# G2-PMS.net
KiCad netlist of a schematic drawn in Altium Designer
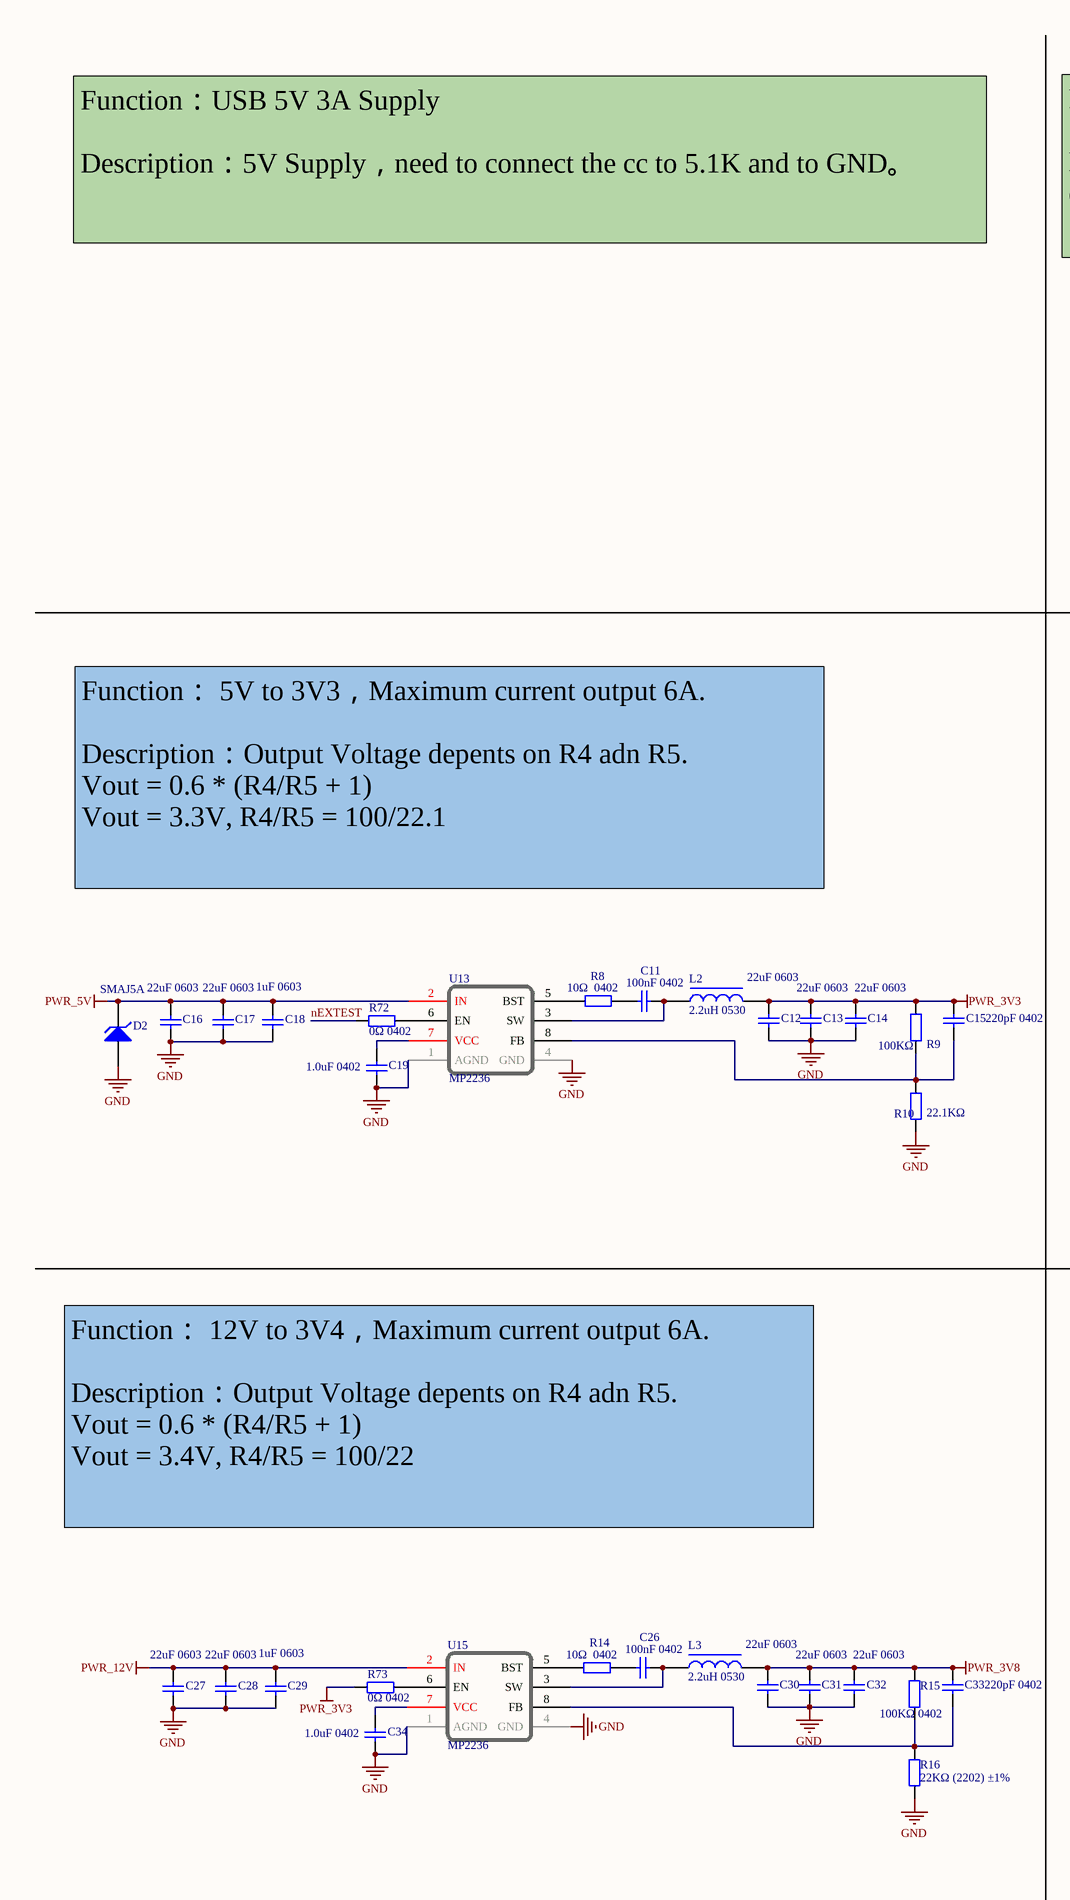
[diagram p0: G2-PMS.SchDoc, left]
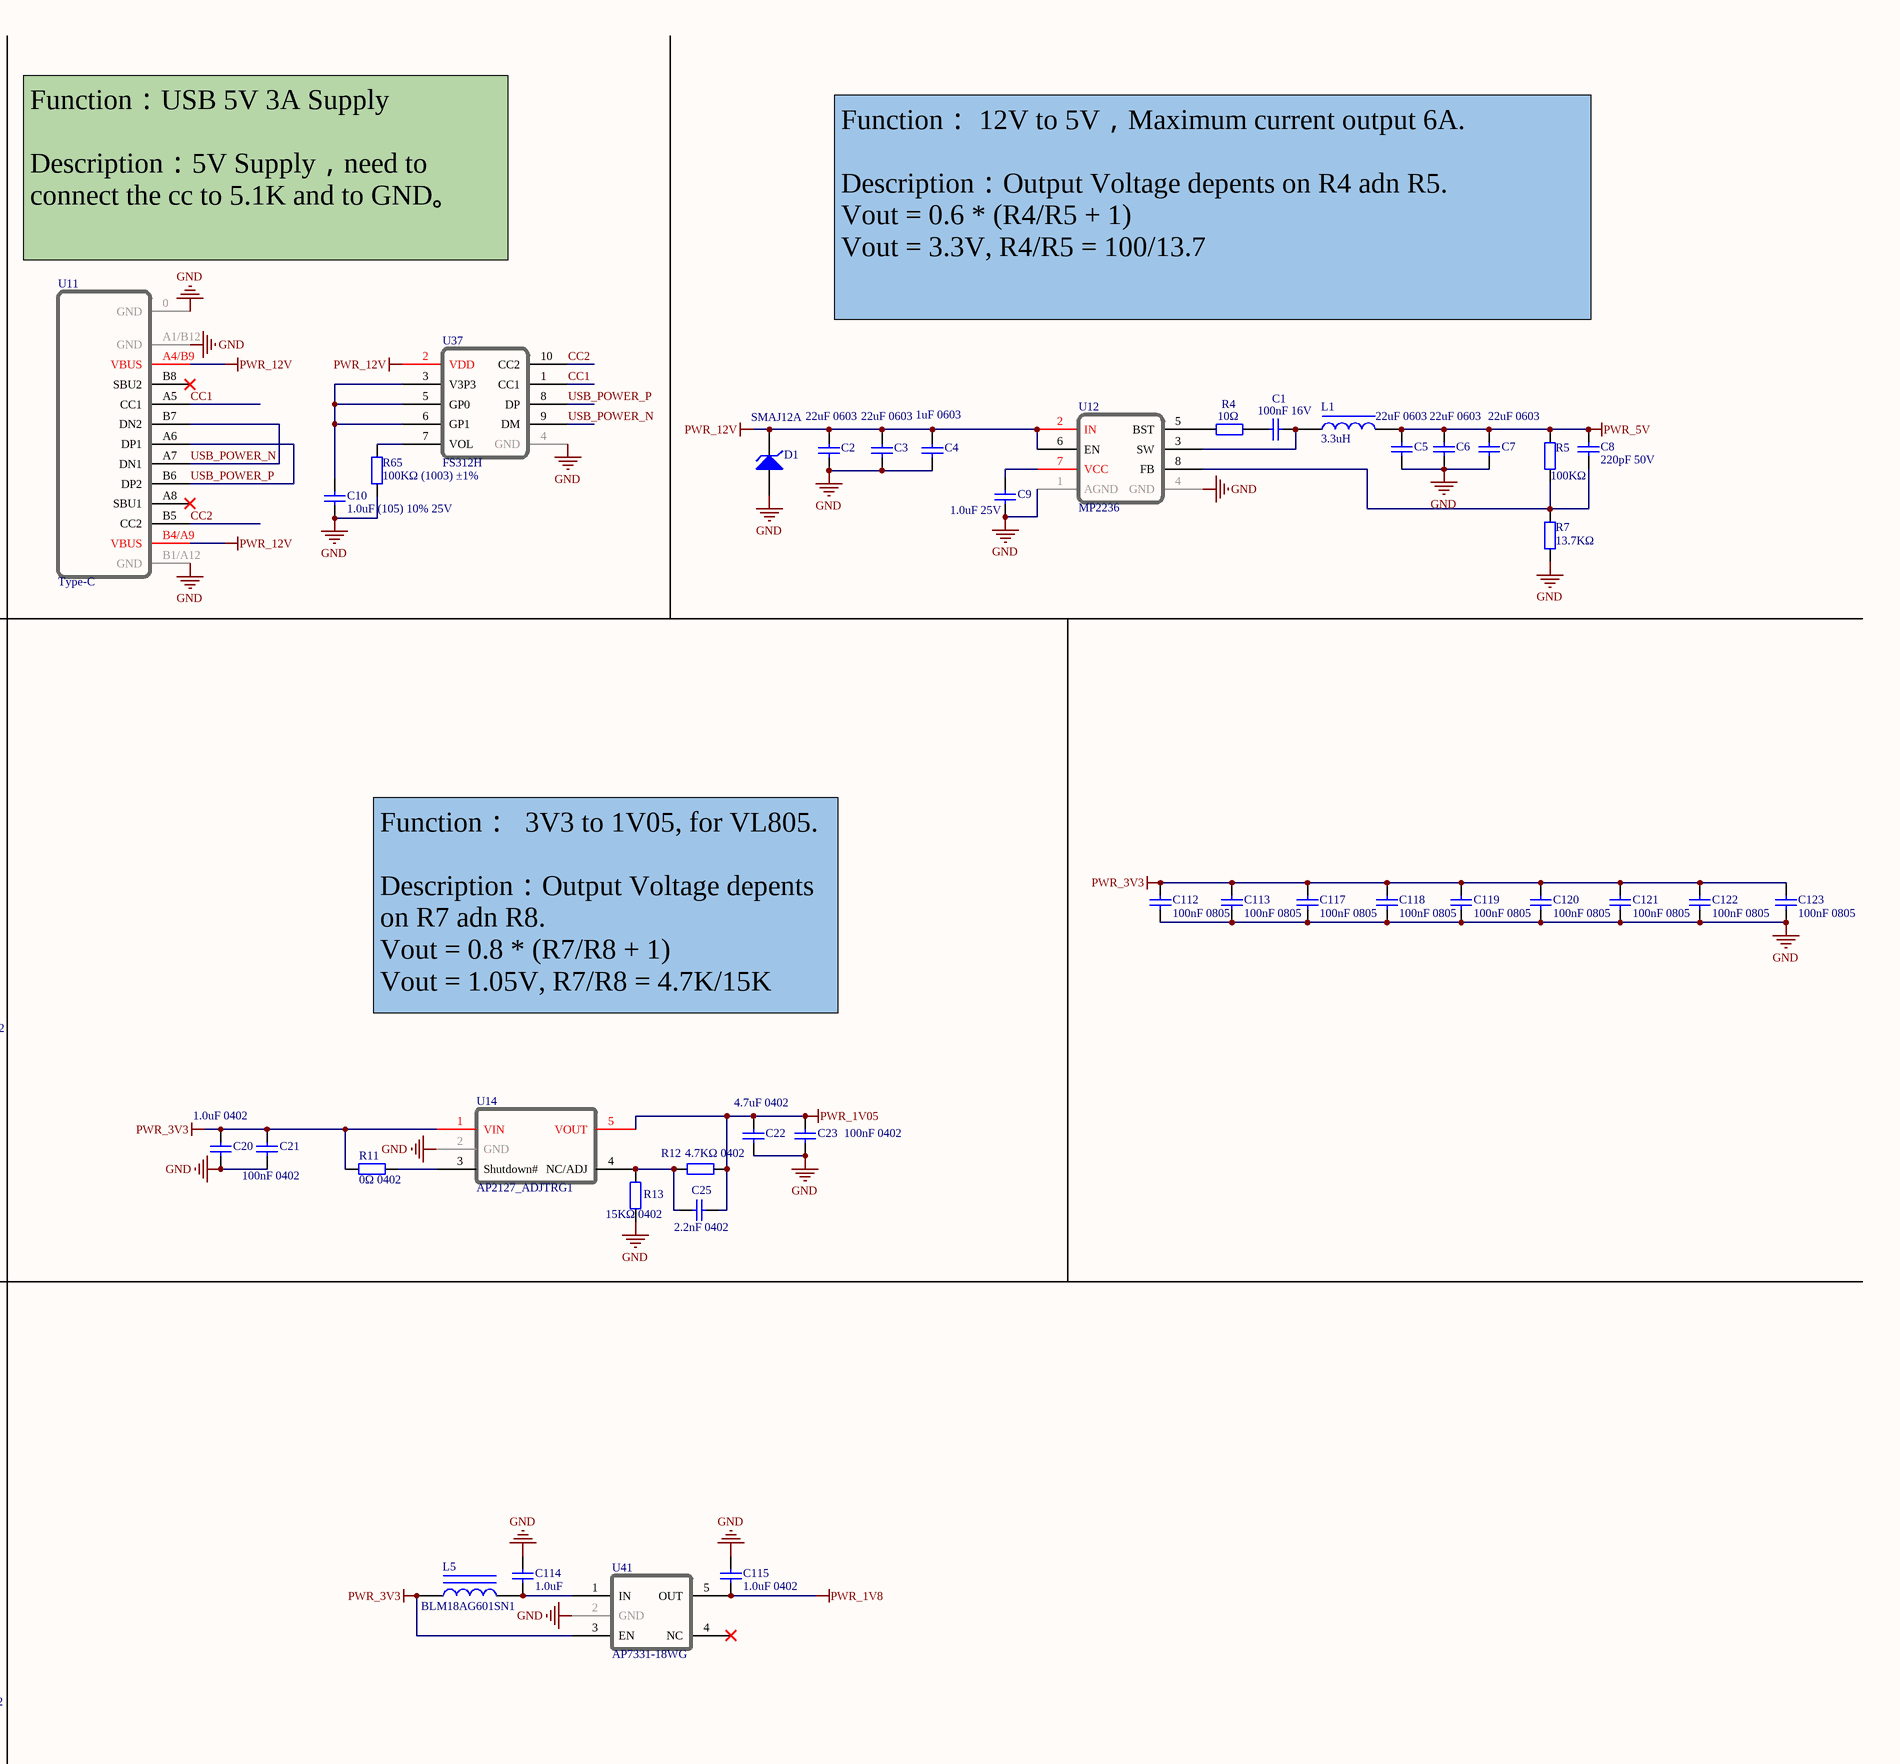
[diagram p1: G2-PMS.SchDoc, right]

(export (version "E")
  (design (tool "Eeschema 10.0.6"))
  (components
    (comp (ref "C1")
      (value "100nF 16V")
      (footprint "0402_C")
      (description "贴片电容")
      (libsource (lib "Miscellaneous Devices LC") (part "0402 100nF (104) 10% 16V"))
    )
    (comp (ref "C2")
      (value "22uF 0603")
      (footprint "0603_C")
      (description "贴片电容")
      (libsource (lib "Miscellaneous Devices LC") (part "0603 22uF (226) 20% 6.3V"))
    )
    (comp (ref "C3")
      (value "22uF 0603")
      (footprint "0603_C")
      (description "贴片电容")
      (libsource (lib "Miscellaneous Devices LC") (part "0603 22uF (226) 20% 6.3V"))
    )
    (comp (ref "C4")
      (value "1uF 0603")
      (footprint "0603_C")
      (description "贴片电容")
      (libsource (lib "Miscellaneous Devices LC") (part "0603 1uF (105) 10% 50V"))
    )
    (comp (ref "C5")
      (value "22uF 0603")
      (footprint "0603_C")
      (description "贴片电容")
      (libsource (lib "Miscellaneous Devices LC") (part "0603 22uF (226) 20% 6.3V"))
    )
    (comp (ref "C6")
      (value "22uF 0603")
      (footprint "0603_C")
      (description "贴片电容")
      (libsource (lib "Miscellaneous Devices LC") (part "0603 22uF (226) 20% 6.3V"))
    )
    (comp (ref "C7")
      (value "22uF 0603")
      (footprint "0603_C")
      (description "贴片电容")
      (libsource (lib "Miscellaneous Devices LC") (part "0603 22uF (226) 20% 6.3V"))
    )
    (comp (ref "C8")
      (value "220pF 50V")
      (footprint "0402_C")
      (description "贴片电容")
      (libsource (lib "Miscellaneous Devices LC") (part "0402 220pF (221) 10% 50V"))
    )
    (comp (ref "C9")
      (value "1.0uF 25V")
      (footprint "0402_C")
      (description "贴片电容")
      (libsource (lib "Miscellaneous Devices LC") (part "0402 1.0uF (105) 10% 25V"))
    )
    (comp (ref "C10")
      (value "1.0uF (105) 10% 25V")
      (footprint "0402_C")
      (description "贴片电容")
      (libsource (lib "Miscellaneous Devices LC") (part "0402 1.0uF (105) 10% 25V"))
    )
    (comp (ref "C11")
      (value "100nF 0402")
      (footprint "0402_C")
      (description "贴片电容")
      (libsource (lib "Miscellaneous Devices LC") (part "0402 100nF (104) 10% 16V"))
    )
    (comp (ref "C12")
      (value "22uF 0603")
      (footprint "0603_C")
      (description "贴片电容")
      (libsource (lib "Miscellaneous Devices LC") (part "0603 22uF (226) 20% 6.3V"))
    )
    (comp (ref "C13")
      (value "22uF 0603")
      (footprint "0603_C")
      (description "贴片电容")
      (libsource (lib "Miscellaneous Devices LC") (part "0603 22uF (226) 20% 6.3V"))
    )
    (comp (ref "C14")
      (value "22uF 0603")
      (footprint "0603_C")
      (description "贴片电容")
      (libsource (lib "Miscellaneous Devices LC") (part "0603 22uF (226) 20% 6.3V"))
    )
    (comp (ref "C15")
      (value "220pF 0402")
      (footprint "0402_C")
      (description "贴片电容")
      (libsource (lib "Miscellaneous Devices LC") (part "0402 220pF (221) 10% 50V"))
    )
    (comp (ref "C16")
      (value "22uF 0603")
      (footprint "0603_C")
      (description "贴片电容")
      (libsource (lib "Miscellaneous Devices LC") (part "0603 22uF (226) 20% 6.3V"))
    )
    (comp (ref "C17")
      (value "22uF 0603")
      (footprint "0603_C")
      (description "贴片电容")
      (libsource (lib "Miscellaneous Devices LC") (part "0603 22uF (226) 20% 6.3V"))
    )
    (comp (ref "C18")
      (value "1uF 0603")
      (footprint "0603_C")
      (description "贴片电容")
      (libsource (lib "Miscellaneous Devices LC") (part "0603 1uF (105) 10% 50V"))
    )
    (comp (ref "C19")
      (value "1.0uF 0402")
      (footprint "0402_C")
      (description "贴片电容")
      (libsource (lib "Miscellaneous Devices LC") (part "0402 1.0uF (105) 10% 25V"))
    )
    (comp (ref "C20")
      (value "1.0uF 0402")
      (footprint "0402_C")
      (description "贴片电容")
      (libsource (lib "Miscellaneous Devices LC") (part "0402 1.0uF (105) 10% 25V"))
    )
    (comp (ref "C21")
      (value "100nF 0402")
      (footprint "0402_C")
      (description "贴片电容")
      (libsource (lib "Miscellaneous Devices LC") (part "0402 100nF (104) 10% 16V"))
    )
    (comp (ref "C22")
      (value "4.7uF 0402")
      (footprint "0402_C")
      (description "贴片电容")
      (libsource (lib "Miscellaneous Devices LC") (part "0402 4.7uF (475) 20% 10V"))
    )
    (comp (ref "C23")
      (value "100nF 0402")
      (footprint "0402_C")
      (description "贴片电容")
      (libsource (lib "Miscellaneous Devices LC") (part "0402 100nF (104) 10% 16V"))
    )
    (comp (ref "C25")
      (value "2.2nF 0402")
      (footprint "0402_C")
      (description "贴片电容")
      (libsource (lib "Miscellaneous Devices LC") (part "0402 2.2nF (222) 10% 50V"))
    )
    (comp (ref "C26")
      (value "100nF 0402")
      (footprint "0402_C")
      (description "贴片电容")
      (libsource (lib "Miscellaneous Devices LC") (part "0402 100nF (104) 10% 16V"))
    )
    (comp (ref "C27")
      (value "22uF 0603")
      (footprint "0603_C")
      (description "贴片电容")
      (libsource (lib "Miscellaneous Devices LC") (part "0603 22uF (226) 20% 6.3V"))
    )
    (comp (ref "C28")
      (value "22uF 0603")
      (footprint "0603_C")
      (description "贴片电容")
      (libsource (lib "Miscellaneous Devices LC") (part "0603 22uF (226) 20% 6.3V"))
    )
    (comp (ref "C29")
      (value "1uF 0603")
      (footprint "0603_C")
      (description "贴片电容")
      (libsource (lib "Miscellaneous Devices LC") (part "0603 1uF (105) 10% 50V"))
    )
    (comp (ref "C30")
      (value "22uF 0603")
      (footprint "0603_C")
      (description "贴片电容")
      (libsource (lib "Miscellaneous Devices LC") (part "0603 22uF (226) 20% 6.3V"))
    )
    (comp (ref "C31")
      (value "22uF 0603")
      (footprint "0603_C")
      (description "贴片电容")
      (libsource (lib "Miscellaneous Devices LC") (part "0603 22uF (226) 20% 6.3V"))
    )
    (comp (ref "C32")
      (value "22uF 0603")
      (footprint "0603_C")
      (description "贴片电容")
      (libsource (lib "Miscellaneous Devices LC") (part "0603 22uF (226) 20% 6.3V"))
    )
    (comp (ref "C33")
      (value "220pF 0402")
      (footprint "0402_C")
      (description "贴片电容")
      (libsource (lib "Miscellaneous Devices LC") (part "0402 220pF (221) 10% 50V"))
    )
    (comp (ref "C34")
      (value "1.0uF 0402")
      (footprint "0402_C")
      (description "贴片电容")
      (libsource (lib "Miscellaneous Devices LC") (part "0402 1.0uF (105) 10% 25V"))
    )
    (comp (ref "C112")
      (value "100nF 0805")
      (footprint "0805_C")
      (description "贴片电容")
      (libsource (lib "Miscellaneous Devices LC") (part "0805 100nF(104) 10% 50V"))
    )
    (comp (ref "C113")
      (value "100nF 0805")
      (footprint "0805_C")
      (description "贴片电容")
      (libsource (lib "Miscellaneous Devices LC") (part "0805 100nF(104) 10% 50V"))
    )
    (comp (ref "C114")
      (value "1.0uF")
      (footprint "0402_C")
      (description "贴片电容")
      (libsource (lib "Miscellaneous Devices LC") (part "0402 1.0uF (105) 10% 25V"))
    )
    (comp (ref "C115")
      (value "1.0uF 0402")
      (footprint "0402_C")
      (description "贴片电容")
      (libsource (lib "Miscellaneous Devices LC") (part "0402 1.0uF (105) 10% 25V"))
    )
    (comp (ref "C117")
      (value "100nF 0805")
      (footprint "0805_C")
      (description "贴片电容")
      (libsource (lib "Miscellaneous Devices LC") (part "0805 100nF(104) 10% 50V"))
    )
    (comp (ref "C118")
      (value "100nF 0805")
      (footprint "0805_C")
      (description "贴片电容")
      (libsource (lib "Miscellaneous Devices LC") (part "0805 100nF(104) 10% 50V"))
    )
    (comp (ref "C119")
      (value "100nF 0805")
      (footprint "0805_C")
      (description "贴片电容")
      (libsource (lib "Miscellaneous Devices LC") (part "0805 100nF(104) 10% 50V"))
    )
    (comp (ref "C120")
      (value "100nF 0805")
      (footprint "0805_C")
      (description "贴片电容")
      (libsource (lib "Miscellaneous Devices LC") (part "0805 100nF(104) 10% 50V"))
    )
    (comp (ref "C121")
      (value "100nF 0805")
      (footprint "0805_C")
      (description "贴片电容")
      (libsource (lib "Miscellaneous Devices LC") (part "0805 100nF(104) 10% 50V"))
    )
    (comp (ref "C122")
      (value "100nF 0805")
      (footprint "0805_C")
      (description "贴片电容")
      (libsource (lib "Miscellaneous Devices LC") (part "0805 100nF(104) 10% 50V"))
    )
    (comp (ref "C123")
      (value "100nF 0805")
      (footprint "0805_C")
      (description "贴片电容")
      (libsource (lib "Miscellaneous Devices LC") (part "0805 100nF(104) 10% 50V"))
    )
    (comp (ref "D1")
      (value "SMAJ12A")
      (footprint "SMAJ12A")
      (description "TVS")
      (libsource (lib "Mars") (part "SMAJ12A"))
    )
    (comp (ref "D2")
      (value "SMAJ5A")
      (footprint "SMAJ5A")
      (description "TVS")
      (libsource (lib "bohao") (part "SMAJ5A"))
    )
    (comp (ref "L1")
      (value "3.3uH")
      (footprint "0530")
      (description "3.3uH 0630")
      (libsource (lib "Mars") (part "3.3uH"))
    )
    (comp (ref "L2")
      (value "2.2uH 0530")
      (footprint "0530")
      (description "2.2uH 0630")
      (libsource (lib "Mars") (part "2.2uH"))
    )
    (comp (ref "L3")
      (value "2.2uH 0530")
      (footprint "0530")
      (description "2.2uH 0630")
      (libsource (lib "Mars") (part "2.2uH"))
    )
    (comp (ref "L5")
      (value "BLM18AG601SN1")
      (footprint "0603_L")
      (description "贴片电感")
      (libsource (lib "Miscellaneous Devices LC") (part "0603 10uH 10%"))
    )
    (comp (ref "R4")
      (value "10Ω")
      (footprint "0402_R")
      (description "贴片电阻")
      (libsource (lib "Miscellaneous Devices LC") (part "0402 10Ω (10R0) 1%"))
    )
    (comp (ref "R5")
      (value "100KΩ")
      (footprint "0402_R")
      (description "贴片电阻")
      (libsource (lib "Miscellaneous Devices LC") (part "0402 100KΩ (1003) 1%"))
    )
    (comp (ref "R7")
      (value "13.7KΩ")
      (footprint "0402_R")
      (description "贴片电阻")
      (libsource (lib "Miscellaneous Devices LC") (part "0402 10KΩ (1002) 1%"))
    )
    (comp (ref "R8")
      (value "10Ω  0402")
      (footprint "0402_R")
      (description "贴片电阻")
      (libsource (lib "Miscellaneous Devices LC") (part "0402 10Ω (10R0) 1%"))
    )
    (comp (ref "R9")
      (value "100KΩ")
      (footprint "0402_R")
      (description "贴片电阻")
      (libsource (lib "Miscellaneous Devices LC") (part "0402 100KΩ (1003) 1%"))
    )
    (comp (ref "R10")
      (value "22.1KΩ")
      (footprint "0402_R")
      (description "贴片电阻")
      (libsource (lib "Miscellaneous Devices LC") (part "0402 10KΩ (1002) 1%"))
    )
    (comp (ref "R11")
      (value "0Ω 0402")
      (footprint "0402_R")
      (description "贴片电阻")
      (libsource (lib "Miscellaneous Devices LC") (part "0402 0Ω (0R0) 1%"))
    )
    (comp (ref "R12")
      (value "4.7KΩ 0402")
      (footprint "0402_R")
      (description "贴片电阻")
      (libsource (lib "Miscellaneous Devices LC") (part "0402 4.7KΩ (4701) 1%"))
    )
    (comp (ref "R13")
      (value "15KΩ 0402")
      (footprint "0402_R")
      (description "贴片电阻")
      (libsource (lib "Miscellaneous Devices LC") (part "0402 15KΩ (1502) 1%"))
    )
    (comp (ref "R14")
      (value "10Ω  0402")
      (footprint "0402_R")
      (description "贴片电阻")
      (libsource (lib "Miscellaneous Devices LC") (part "0402 10Ω (10R0) 1%"))
    )
    (comp (ref "R15")
      (value "100KΩ 0402")
      (footprint "0402_R")
      (description "贴片电阻")
      (libsource (lib "Miscellaneous Devices LC") (part "0402 100KΩ (1003) 1%"))
    )
    (comp (ref "R16")
      (value "22KΩ (2202) ±1%")
      (footprint "0402_R")
      (description "贴片电阻")
      (libsource (lib "Miscellaneous Devices LC") (part "0402 22KΩ (2202) 1%"))
    )
    (comp (ref "R65")
      (value "100KΩ (1003) ±1%")
      (footprint "0402_R")
      (description "贴片电阻")
      (libsource (lib "Miscellaneous Devices LC") (part "0402 100KΩ (1003) 1%"))
    )
    (comp (ref "R72")
      (value "0Ω 0402")
      (footprint "0402_R")
      (description "贴片电阻")
      (libsource (lib "Miscellaneous Devices LC") (part "0402 0Ω (0R0) 1%"))
    )
    (comp (ref "R73")
      (value "0Ω 0402")
      (footprint "0402_R")
      (description "贴片电阻")
      (libsource (lib "Miscellaneous Devices LC") (part "0402 0Ω (0R0) 1%"))
    )
    (comp (ref "U11")
      (value "Type-C")
      (footprint "Type-C-16P")
      (description "Type-C-16P")
      (libsource (lib "Mars") (part "Type-C-16P"))
    )
    (comp (ref "U12")
      (value "MP2236")
      (footprint "MP2236")
      (description "Vin=18, Iout=6A")
      (libsource (lib "bohao") (part "MP2236"))
    )
    (comp (ref "U13")
      (value "MP2236")
      (footprint "MP2236")
      (description "Vin=18, Iout=6A")
      (libsource (lib "bohao") (part "MP2236"))
    )
    (comp (ref "U14")
      (value "AP2127_ADJTRG1")
      (footprint "AP2127K")
      (description "3.3V-1.05V")
      (libsource (lib "bohao") (part "AP2127_ADJTRG1"))
    )
    (comp (ref "U15")
      (value "MP2236")
      (footprint "MP2236")
      (description "Vin=18, Iout=6A")
      (libsource (lib "bohao") (part "MP2236"))
    )
    (comp (ref "U37")
      (value "FS312H")
      (footprint "FS312H")
      (description "USB POWER PD 20V")
      (libsource (lib "Mars") (part "FS312H"))
    )
    (comp (ref "U41")
      (value "AP7331-18WG")
      (footprint "AP7331-18WG")
      (description "Camera 1.8V")
      (libsource (lib "bohao") (part "AP7331-18WG"))
    )
  )
  (nets
    (net (code "2") (name "/CC1") (class "Default")
      (node (ref "U11") (pin "A5") (pinfunction "CC1_A5") (pintype "passive"))
      (node (ref "U37") (pin "1") (pinfunction "CC1_1") (pintype "passive"))
    )
    (net (code "3") (name "/CC2") (class "Default")
      (node (ref "U11") (pin "B5") (pinfunction "CC2_B5") (pintype "passive"))
      (node (ref "U37") (pin "10") (pinfunction "CC2_10") (pintype "passive"))
    )
    (net (code "4") (name "/USB_POWER_N") (class "Default")
      (node (ref "U11") (pin "A7") (pinfunction "DN1_A7") (pintype "passive"))
      (node (ref "U11") (pin "B7") (pinfunction "DN2_B7") (pintype "passive"))
      (node (ref "U37") (pin "9") (pinfunction "DM_9") (pintype "passive"))
    )
    (net (code "5") (name "/USB_POWER_P") (class "Default")
      (node (ref "U11") (pin "A6") (pinfunction "DP1_A6") (pintype "passive"))
      (node (ref "U11") (pin "B6") (pinfunction "DP2_B6") (pintype "passive"))
      (node (ref "U37") (pin "8") (pinfunction "DP_8") (pintype "passive"))
    )
    (net (code "6") (name "/nEXTEST") (class "Default")
      (node (ref "R72") (pin "1") (pinfunction "1_1") (pintype "passive"))
    )
    (net (code "7") (name "GND") (class "Default")
      (node (ref "C10") (pin "1") (pinfunction "1_1") (pintype "passive"))
      (node (ref "C112") (pin "1") (pinfunction "1_1") (pintype "passive"))
      (node (ref "C113") (pin "1") (pinfunction "1_1") (pintype "passive"))
      (node (ref "C114") (pin "2") (pinfunction "2_2") (pintype "passive"))
      (node (ref "C115") (pin "1") (pinfunction "1_1") (pintype "passive"))
      (node (ref "C117") (pin "1") (pinfunction "1_1") (pintype "passive"))
      (node (ref "C118") (pin "1") (pinfunction "1_1") (pintype "passive"))
      (node (ref "C119") (pin "1") (pinfunction "1_1") (pintype "passive"))
      (node (ref "C12") (pin "1") (pinfunction "1_1") (pintype "passive"))
      (node (ref "C120") (pin "1") (pinfunction "1_1") (pintype "passive"))
      (node (ref "C121") (pin "1") (pinfunction "1_1") (pintype "passive"))
      (node (ref "C122") (pin "1") (pinfunction "1_1") (pintype "passive"))
      (node (ref "C123") (pin "1") (pinfunction "1_1") (pintype "passive"))
      (node (ref "C13") (pin "1") (pinfunction "1_1") (pintype "passive"))
      (node (ref "C14") (pin "1") (pinfunction "1_1") (pintype "passive"))
      (node (ref "C16") (pin "1") (pinfunction "1_1") (pintype "passive"))
      (node (ref "C17") (pin "1") (pinfunction "1_1") (pintype "passive"))
      (node (ref "C18") (pin "1") (pinfunction "1_1") (pintype "passive"))
      (node (ref "C19") (pin "1") (pinfunction "1_1") (pintype "passive"))
      (node (ref "C2") (pin "1") (pinfunction "1_1") (pintype "passive"))
      (node (ref "C20") (pin "1") (pinfunction "1_1") (pintype "passive"))
      (node (ref "C21") (pin "1") (pinfunction "1_1") (pintype "passive"))
      (node (ref "C22") (pin "1") (pinfunction "1_1") (pintype "passive"))
      (node (ref "C23") (pin "1") (pinfunction "1_1") (pintype "passive"))
      (node (ref "C27") (pin "1") (pinfunction "1_1") (pintype "passive"))
      (node (ref "C28") (pin "1") (pinfunction "1_1") (pintype "passive"))
      (node (ref "C29") (pin "1") (pinfunction "1_1") (pintype "passive"))
      (node (ref "C3") (pin "1") (pinfunction "1_1") (pintype "passive"))
      (node (ref "C30") (pin "1") (pinfunction "1_1") (pintype "passive"))
      (node (ref "C31") (pin "1") (pinfunction "1_1") (pintype "passive"))
      (node (ref "C32") (pin "1") (pinfunction "1_1") (pintype "passive"))
      (node (ref "C34") (pin "1") (pinfunction "1_1") (pintype "passive"))
      (node (ref "C4") (pin "1") (pinfunction "1_1") (pintype "passive"))
      (node (ref "C5") (pin "1") (pinfunction "1_1") (pintype "passive"))
      (node (ref "C6") (pin "1") (pinfunction "1_1") (pintype "passive"))
      (node (ref "C7") (pin "1") (pinfunction "1_1") (pintype "passive"))
      (node (ref "C9") (pin "1") (pinfunction "1_1") (pintype "passive"))
      (node (ref "D1") (pin "1") (pinfunction "A_1") (pintype "passive"))
      (node (ref "D2") (pin "1") (pinfunction "A_1") (pintype "passive"))
      (node (ref "R10") (pin "1") (pinfunction "1_1") (pintype "passive"))
      (node (ref "R13") (pin "1") (pinfunction "1_1") (pintype "passive"))
      (node (ref "R16") (pin "1") (pinfunction "1_1") (pintype "passive"))
      (node (ref "R65") (pin "1") (pinfunction "1_1") (pintype "passive"))
      (node (ref "R7") (pin "1") (pinfunction "1_1") (pintype "passive"))
      (node (ref "U11") (pin "0") (pinfunction "GND_0") (pintype "passive"))
      (node (ref "U11") (pin "A1/B12") (pinfunction "GND_A1/B12") (pintype "passive"))
      (node (ref "U11") (pin "B1/A12") (pinfunction "GND_B1/A12") (pintype "passive"))
      (node (ref "U12") (pin "1") (pinfunction "AGND_1") (pintype "passive"))
      (node (ref "U12") (pin "4") (pinfunction "GND_4") (pintype "passive"))
      (node (ref "U13") (pin "1") (pinfunction "AGND_1") (pintype "passive"))
      (node (ref "U13") (pin "4") (pinfunction "GND_4") (pintype "passive"))
      (node (ref "U14") (pin "2") (pinfunction "GND_2") (pintype "passive"))
      (node (ref "U15") (pin "1") (pinfunction "AGND_1") (pintype "passive"))
      (node (ref "U15") (pin "4") (pinfunction "GND_4") (pintype "passive"))
      (node (ref "U37") (pin "4") (pinfunction "GND_4") (pintype "passive"))
      (node (ref "U41") (pin "2") (pinfunction "GND_2") (pintype "passive"))
    )
    (net (code "8") (name "Net-(C1-Pad1)") (class "Default")
      (node (ref "C1") (pin "1") (pinfunction "1_1") (pintype "passive"))
      (node (ref "R4") (pin "2") (pinfunction "2_2") (pintype "passive"))
    )
    (net (code "9") (name "Net-(C11-Pad1)") (class "Default")
      (node (ref "C11") (pin "1") (pinfunction "1_1") (pintype "passive"))
      (node (ref "R8") (pin "2") (pinfunction "2_2") (pintype "passive"))
    )
    (net (code "10") (name "Net-(C26-Pad1)") (class "Default")
      (node (ref "C26") (pin "1") (pinfunction "1_1") (pintype "passive"))
      (node (ref "R14") (pin "2") (pinfunction "2_2") (pintype "passive"))
    )
    (net (code "11") (name "Net-(U12-BST)") (class "Default")
      (node (ref "R4") (pin "1") (pinfunction "1_1") (pintype "passive"))
      (node (ref "U12") (pin "5") (pinfunction "BST_5") (pintype "passive"))
    )
    (net (code "12") (name "Net-(U12-FB)") (class "Default")
      (node (ref "C8") (pin "1") (pinfunction "1_1") (pintype "passive"))
      (node (ref "R5") (pin "1") (pinfunction "1_1") (pintype "passive"))
      (node (ref "R7") (pin "2") (pinfunction "2_2") (pintype "passive"))
      (node (ref "U12") (pin "8") (pinfunction "FB_8") (pintype "passive"))
    )
    (net (code "13") (name "Net-(U12-SW)") (class "Default")
      (node (ref "C1") (pin "2") (pinfunction "2_2") (pintype "passive"))
      (node (ref "L1") (pin "1") (pinfunction "1_1") (pintype "passive"))
      (node (ref "U12") (pin "3") (pinfunction "SW_3") (pintype "passive"))
    )
    (net (code "14") (name "Net-(U12-VCC)") (class "Default")
      (node (ref "C9") (pin "2") (pinfunction "2_2") (pintype "passive"))
      (node (ref "U12") (pin "7") (pinfunction "VCC_7") (pintype "passive"))
    )
    (net (code "15") (name "Net-(U13-BST)") (class "Default")
      (node (ref "R8") (pin "1") (pinfunction "1_1") (pintype "passive"))
      (node (ref "U13") (pin "5") (pinfunction "BST_5") (pintype "passive"))
    )
    (net (code "16") (name "Net-(U13-EN)") (class "Default")
      (node (ref "R72") (pin "2") (pinfunction "2_2") (pintype "passive"))
      (node (ref "U13") (pin "6") (pinfunction "EN_6") (pintype "passive"))
    )
    (net (code "17") (name "Net-(U13-FB)") (class "Default")
      (node (ref "C15") (pin "1") (pinfunction "1_1") (pintype "passive"))
      (node (ref "R10") (pin "2") (pinfunction "2_2") (pintype "passive"))
      (node (ref "R9") (pin "1") (pinfunction "1_1") (pintype "passive"))
      (node (ref "U13") (pin "8") (pinfunction "FB_8") (pintype "passive"))
    )
    (net (code "18") (name "Net-(U13-SW)") (class "Default")
      (node (ref "C11") (pin "2") (pinfunction "2_2") (pintype "passive"))
      (node (ref "L2") (pin "1") (pinfunction "1_1") (pintype "passive"))
      (node (ref "U13") (pin "3") (pinfunction "SW_3") (pintype "passive"))
    )
    (net (code "19") (name "Net-(U13-VCC)") (class "Default")
      (node (ref "C19") (pin "2") (pinfunction "2_2") (pintype "passive"))
      (node (ref "U13") (pin "7") (pinfunction "VCC_7") (pintype "passive"))
    )
    (net (code "20") (name "Net-(U14-NC{slash}ADJ)") (class "Default")
      (node (ref "C25") (pin "1") (pinfunction "1_1") (pintype "passive"))
      (node (ref "R12") (pin "1") (pinfunction "1_1") (pintype "passive"))
      (node (ref "R13") (pin "2") (pinfunction "2_2") (pintype "passive"))
      (node (ref "U14") (pin "4") (pinfunction "NC/ADJ_4") (pintype "passive"))
    )
    (net (code "21") (name "Net-(U14-Shutdown#)") (class "Default")
      (node (ref "R11") (pin "2") (pinfunction "2_2") (pintype "passive"))
      (node (ref "U14") (pin "3") (pinfunction "Shutdown#_3") (pintype "passive"))
    )
    (net (code "22") (name "Net-(U15-BST)") (class "Default")
      (node (ref "R14") (pin "1") (pinfunction "1_1") (pintype "passive"))
      (node (ref "U15") (pin "5") (pinfunction "BST_5") (pintype "passive"))
    )
    (net (code "23") (name "Net-(U15-EN)") (class "Default")
      (node (ref "R73") (pin "2") (pinfunction "2_2") (pintype "passive"))
      (node (ref "U15") (pin "6") (pinfunction "EN_6") (pintype "passive"))
    )
    (net (code "24") (name "Net-(U15-FB)") (class "Default")
      (node (ref "C33") (pin "1") (pinfunction "1_1") (pintype "passive"))
      (node (ref "R15") (pin "1") (pinfunction "1_1") (pintype "passive"))
      (node (ref "R16") (pin "2") (pinfunction "2_2") (pintype "passive"))
      (node (ref "U15") (pin "8") (pinfunction "FB_8") (pintype "passive"))
    )
    (net (code "25") (name "Net-(U15-SW)") (class "Default")
      (node (ref "C26") (pin "2") (pinfunction "2_2") (pintype "passive"))
      (node (ref "L3") (pin "1") (pinfunction "1_1") (pintype "passive"))
      (node (ref "U15") (pin "3") (pinfunction "SW_3") (pintype "passive"))
    )
    (net (code "26") (name "Net-(U15-VCC)") (class "Default")
      (node (ref "C34") (pin "2") (pinfunction "2_2") (pintype "passive"))
      (node (ref "U15") (pin "7") (pinfunction "VCC_7") (pintype "passive"))
    )
    (net (code "27") (name "Net-(U37-GP0)") (class "Default")
      (node (ref "C10") (pin "2") (pinfunction "2_2") (pintype "passive"))
      (node (ref "U37") (pin "3") (pinfunction "V3P3_3") (pintype "passive"))
      (node (ref "U37") (pin "5") (pinfunction "GP0_5") (pintype "passive"))
      (node (ref "U37") (pin "6") (pinfunction "GP1_6") (pintype "passive"))
    )
    (net (code "28") (name "Net-(U37-VOL)") (class "Default")
      (node (ref "R65") (pin "2") (pinfunction "2_2") (pintype "passive"))
      (node (ref "U37") (pin "7") (pinfunction "VOL_7") (pintype "passive"))
    )
    (net (code "29") (name "Net-(U41-IN)") (class "Default")
      (node (ref "C114") (pin "1") (pinfunction "1_1") (pintype "passive"))
      (node (ref "L5") (pin "2") (pinfunction "2_2") (pintype "passive"))
      (node (ref "U41") (pin "1") (pinfunction "IN_1") (pintype "passive"))
    )
    (net (code "30") (name "PWR_1V05") (class "Default")
      (node (ref "C22") (pin "2") (pinfunction "2_2") (pintype "passive"))
      (node (ref "C23") (pin "2") (pinfunction "2_2") (pintype "passive"))
      (node (ref "C25") (pin "2") (pinfunction "2_2") (pintype "passive"))
      (node (ref "R12") (pin "2") (pinfunction "2_2") (pintype "passive"))
      (node (ref "U14") (pin "5") (pinfunction "VOUT_5") (pintype "passive"))
    )
    (net (code "31") (name "PWR_1V8") (class "Default")
      (node (ref "C115") (pin "2") (pinfunction "2_2") (pintype "passive"))
      (node (ref "U41") (pin "5") (pinfunction "OUT_5") (pintype "passive"))
    )
    (net (code "32") (name "PWR_3V3") (class "Default")
      (node (ref "C112") (pin "2") (pinfunction "2_2") (pintype "passive"))
      (node (ref "C113") (pin "2") (pinfunction "2_2") (pintype "passive"))
      (node (ref "C117") (pin "2") (pinfunction "2_2") (pintype "passive"))
      (node (ref "C118") (pin "2") (pinfunction "2_2") (pintype "passive"))
      (node (ref "C119") (pin "2") (pinfunction "2_2") (pintype "passive"))
      (node (ref "C12") (pin "2") (pinfunction "2_2") (pintype "passive"))
      (node (ref "C120") (pin "2") (pinfunction "2_2") (pintype "passive"))
      (node (ref "C121") (pin "2") (pinfunction "2_2") (pintype "passive"))
      (node (ref "C122") (pin "2") (pinfunction "2_2") (pintype "passive"))
      (node (ref "C123") (pin "2") (pinfunction "2_2") (pintype "passive"))
      (node (ref "C13") (pin "2") (pinfunction "2_2") (pintype "passive"))
      (node (ref "C14") (pin "2") (pinfunction "2_2") (pintype "passive"))
      (node (ref "C15") (pin "2") (pinfunction "2_2") (pintype "passive"))
      (node (ref "C20") (pin "2") (pinfunction "2_2") (pintype "passive"))
      (node (ref "C21") (pin "2") (pinfunction "2_2") (pintype "passive"))
      (node (ref "L2") (pin "2") (pinfunction "2_2") (pintype "passive"))
      (node (ref "L5") (pin "1") (pinfunction "1_1") (pintype "passive"))
      (node (ref "R11") (pin "1") (pinfunction "1_1") (pintype "passive"))
      (node (ref "R73") (pin "1") (pinfunction "1_1") (pintype "passive"))
      (node (ref "R9") (pin "2") (pinfunction "2_2") (pintype "passive"))
      (node (ref "U14") (pin "1") (pinfunction "VIN_1") (pintype "passive"))
      (node (ref "U41") (pin "3") (pinfunction "EN_3") (pintype "passive"))
    )
    (net (code "33") (name "PWR_3V8") (class "Default")
      (node (ref "C30") (pin "2") (pinfunction "2_2") (pintype "passive"))
      (node (ref "C31") (pin "2") (pinfunction "2_2") (pintype "passive"))
      (node (ref "C32") (pin "2") (pinfunction "2_2") (pintype "passive"))
      (node (ref "C33") (pin "2") (pinfunction "2_2") (pintype "passive"))
      (node (ref "L3") (pin "2") (pinfunction "2_2") (pintype "passive"))
      (node (ref "R15") (pin "2") (pinfunction "2_2") (pintype "passive"))
    )
    (net (code "34") (name "PWR_5V") (class "Default")
      (node (ref "C16") (pin "2") (pinfunction "2_2") (pintype "passive"))
      (node (ref "C17") (pin "2") (pinfunction "2_2") (pintype "passive"))
      (node (ref "C18") (pin "2") (pinfunction "2_2") (pintype "passive"))
      (node (ref "C5") (pin "2") (pinfunction "2_2") (pintype "passive"))
      (node (ref "C6") (pin "2") (pinfunction "2_2") (pintype "passive"))
      (node (ref "C7") (pin "2") (pinfunction "2_2") (pintype "passive"))
      (node (ref "C8") (pin "2") (pinfunction "2_2") (pintype "passive"))
      (node (ref "D2") (pin "2") (pinfunction "C_2") (pintype "passive"))
      (node (ref "L1") (pin "2") (pinfunction "2_2") (pintype "passive"))
      (node (ref "R5") (pin "2") (pinfunction "2_2") (pintype "passive"))
      (node (ref "U13") (pin "2") (pinfunction "IN_2") (pintype "passive"))
    )
    (net (code "35") (name "PWR_12V") (class "Default")
      (node (ref "C2") (pin "2") (pinfunction "2_2") (pintype "passive"))
      (node (ref "C27") (pin "2") (pinfunction "2_2") (pintype "passive"))
      (node (ref "C28") (pin "2") (pinfunction "2_2") (pintype "passive"))
      (node (ref "C29") (pin "2") (pinfunction "2_2") (pintype "passive"))
      (node (ref "C3") (pin "2") (pinfunction "2_2") (pintype "passive"))
      (node (ref "C4") (pin "2") (pinfunction "2_2") (pintype "passive"))
      (node (ref "D1") (pin "2") (pinfunction "C_2") (pintype "passive"))
      (node (ref "U11") (pin "A4/B9") (pinfunction "VBUS_A4/B9") (pintype "passive"))
      (node (ref "U11") (pin "B4/A9") (pinfunction "VBUS_B4/A9") (pintype "passive"))
      (node (ref "U12") (pin "2") (pinfunction "IN_2") (pintype "passive"))
      (node (ref "U12") (pin "6") (pinfunction "EN_6") (pintype "passive"))
      (node (ref "U15") (pin "2") (pinfunction "IN_2") (pintype "passive"))
      (node (ref "U37") (pin "2") (pinfunction "VDD_2") (pintype "passive"))
    )
    (net (code "36") (name "unconnected-(U11-SBU1-PadA8)") (class "Default")
      (node (ref "U11") (pin "A8") (pinfunction "SBU1_A8") (pintype "passive+no_connect"))
    )
    (net (code "37") (name "unconnected-(U11-SBU2-PadB8)") (class "Default")
      (node (ref "U11") (pin "B8") (pinfunction "SBU2_B8") (pintype "passive+no_connect"))
    )
    (net (code "38") (name "unconnected-(U41-NC-Pad4)") (class "Default")
      (node (ref "U41") (pin "4") (pinfunction "NC_4") (pintype "power_in+no_connect"))
    )
  )
)
